# BLE_Bee_v1_0_sch.net
KiCad netlist of a schematic drawn in EAGLE
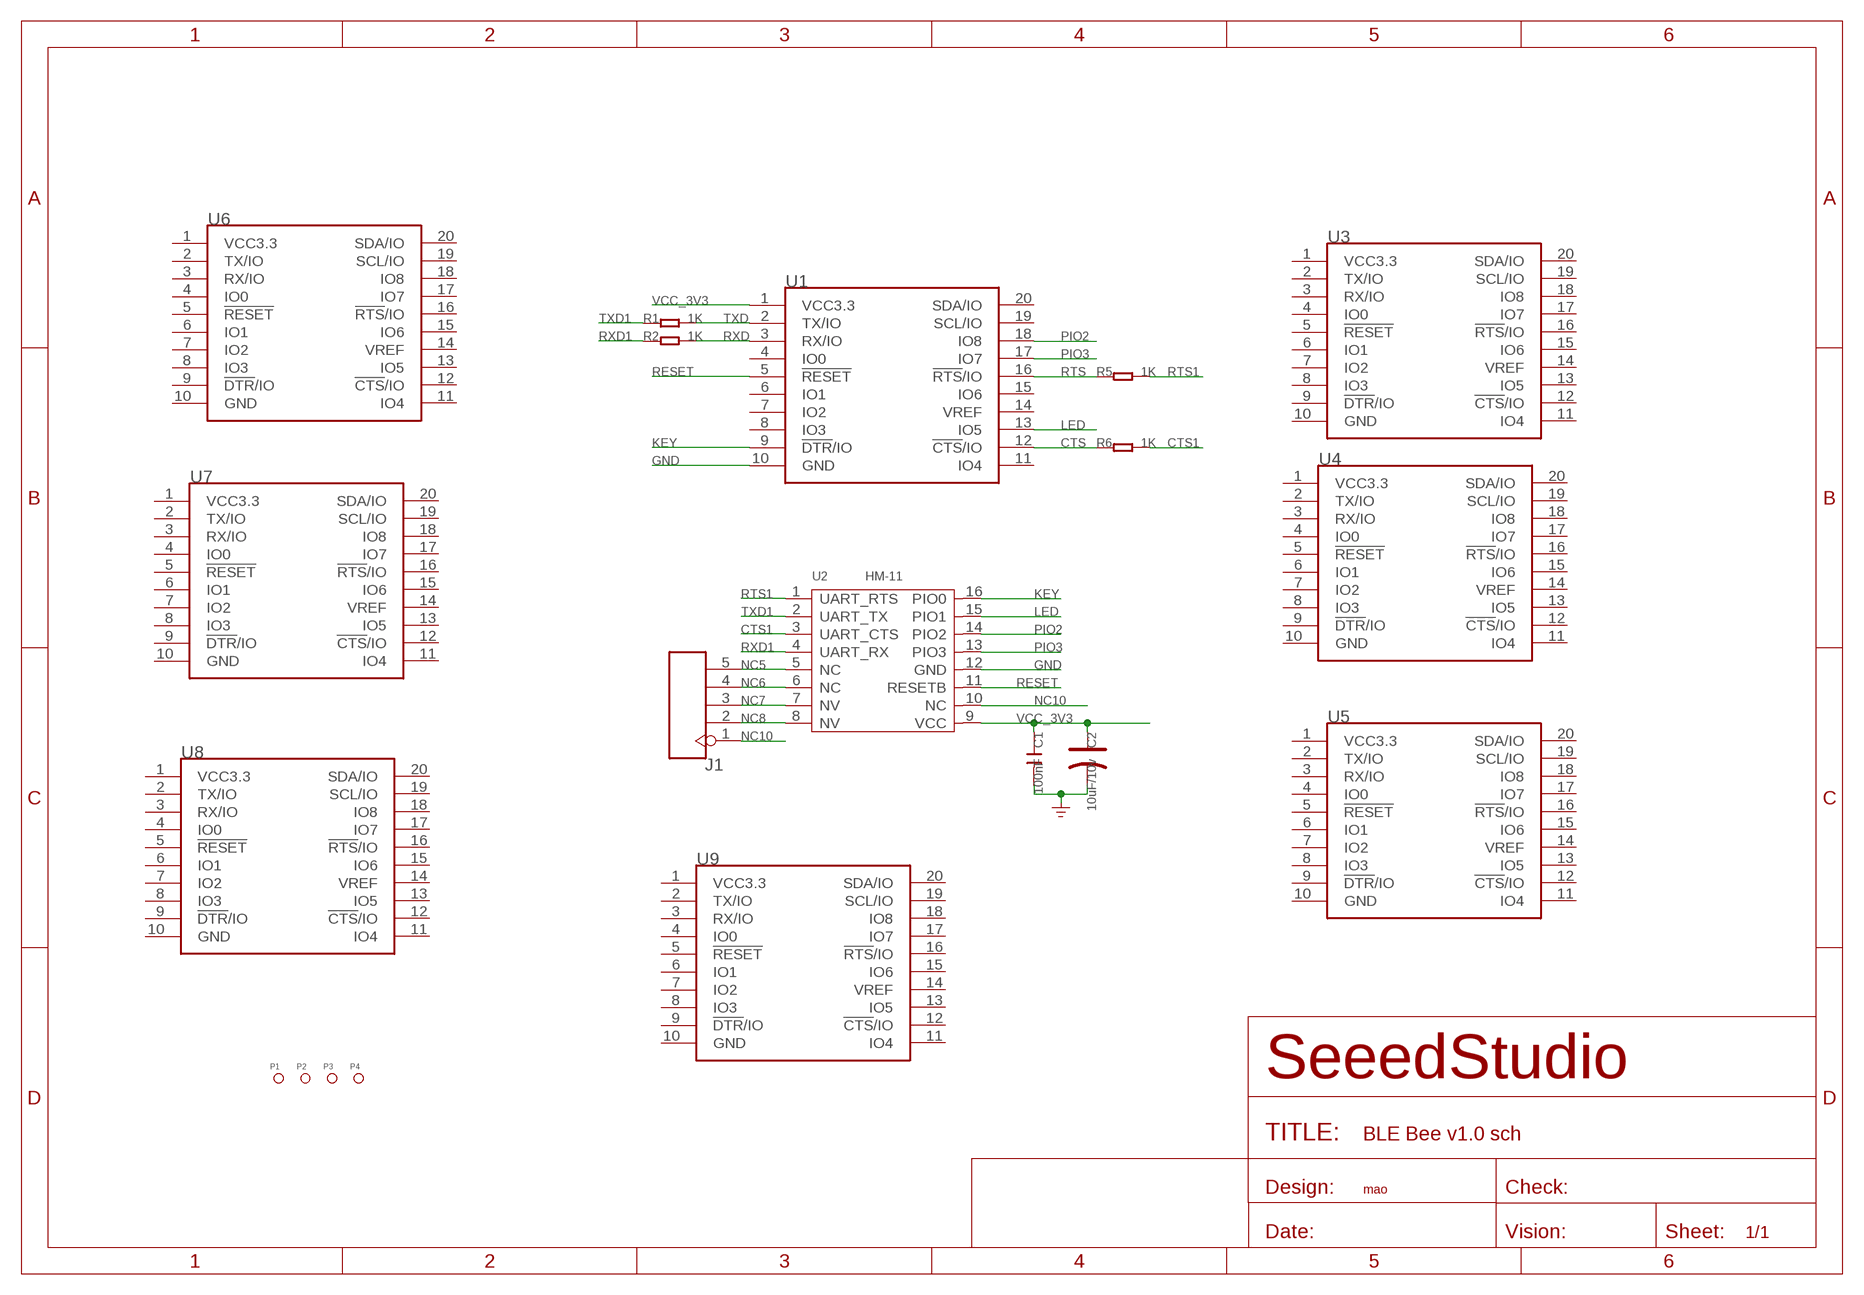
[diagram p0: schematic, sheet 1]

(export (version "E")
  (design (tool "Eeschema 10.0.6"))
  (components
    (comp (ref "C1")
      (value "100nF")
      (footprint "eagle-import:C0603")
      (libsource (lib "eagle-import") (part "C-0603"))
    )
    (comp (ref "C2")
      (value "10uF/10v")
      (footprint "eagle-import:AVX-A")
      (libsource (lib "eagle-import") (part "CAP-AVX-A"))
    )
    (comp (ref "J1")
      (value "HEADER-5P-2.0")
      (footprint "eagle-import:5P-2.0")
      (libsource (lib "eagle-import") (part "HEADER-5P-2.0"))
    )
    (comp (ref "P1")
      (value "PAD-MARK")
      (footprint "eagle-import:ROUND-MARK-1.0")
      (fields (field (name "PARTNO") "DNP"))
      (libsource (lib "eagle-import") (part "PAD-MARK"))
    )
    (comp (ref "P2")
      (value "PAD-MARK")
      (footprint "eagle-import:ROUND-MARK-1.0")
      (fields (field (name "PARTNO") "DNP"))
      (libsource (lib "eagle-import") (part "PAD-MARK"))
    )
    (comp (ref "P3")
      (value "PAD-MARK")
      (footprint "eagle-import:ROUND-MARK-1.0")
      (fields (field (name "PARTNO") "DNP"))
      (libsource (lib "eagle-import") (part "PAD-MARK"))
    )
    (comp (ref "P4")
      (value "PAD-MARK")
      (footprint "eagle-import:ROUND-MARK-1.0")
      (fields (field (name "PARTNO") "DNP"))
      (libsource (lib "eagle-import") (part "PAD-MARK"))
    )
    (comp (ref "R1")
      (value "1K")
      (footprint "eagle-import:R0603")
      (libsource (lib "eagle-import") (part "R-0603"))
    )
    (comp (ref "R2")
      (value "1K")
      (footprint "eagle-import:R0603")
      (libsource (lib "eagle-import") (part "R-0603"))
    )
    (comp (ref "R5")
      (value "1K")
      (footprint "eagle-import:R0603")
      (libsource (lib "eagle-import") (part "R-0603"))
    )
    (comp (ref "R6")
      (value "1K")
      (footprint "eagle-import:R0603")
      (libsource (lib "eagle-import") (part "R-0603"))
    )
    (comp (ref "U1")
      (value "BEE-OPENBEE-DIP")
      (footprint "eagle-import:20P-DIP-2.0")
      (libsource (lib "eagle-import") (part "BEE-OPENBEE-DIP"))
    )
    (comp (ref "U2")
      (value "HM-11")
      (footprint "eagle-import:16P-18.5X13.5X0.8")
      (libsource (lib "eagle-import") (part "HM-11"))
    )
    (comp (ref "U3")
      (value "BEE-OPENBEE-DIP")
      (footprint "eagle-import:20P-DIP-2.0")
      (libsource (lib "eagle-import") (part "BEE-OPENBEE-DIP"))
    )
    (comp (ref "U4")
      (value "BEE-OPENBEE-DIP")
      (footprint "eagle-import:20P-DIP-2.0")
      (libsource (lib "eagle-import") (part "BEE-OPENBEE-DIP"))
    )
    (comp (ref "U5")
      (value "BEE-OPENBEE-DIP")
      (footprint "eagle-import:20P-DIP-2.0")
      (libsource (lib "eagle-import") (part "BEE-OPENBEE-DIP"))
    )
    (comp (ref "U6")
      (value "BEE-OPENBEE-DIP")
      (footprint "eagle-import:20P-DIP-2.0")
      (libsource (lib "eagle-import") (part "BEE-OPENBEE-DIP"))
    )
    (comp (ref "U7")
      (value "BEE-OPENBEE-DIP")
      (footprint "eagle-import:20P-DIP-2.0")
      (libsource (lib "eagle-import") (part "BEE-OPENBEE-DIP"))
    )
    (comp (ref "U8")
      (value "BEE-OPENBEE-DIP")
      (footprint "eagle-import:20P-DIP-2.0")
      (libsource (lib "eagle-import") (part "BEE-OPENBEE-DIP"))
    )
    (comp (ref "U9")
      (value "BEE-OPENBEE-DIP")
      (footprint "eagle-import:20P-DIP-2.0")
      (libsource (lib "eagle-import") (part "BEE-OPENBEE-DIP"))
    )
  )
  (nets
    (net (code "1") (name "/CTS") (class "Default")
      (node (ref "R6") (pin "1") (pinfunction "1_1") (pintype "passive"))
      (node (ref "U1") (pin "12") (pinfunction "~{CTS}/IO_12") (pintype "bidirectional"))
    )
    (net (code "2") (name "/CTS1") (class "Default")
      (node (ref "R6") (pin "2") (pinfunction "2_2") (pintype "passive"))
      (node (ref "U2") (pin "3") (pinfunction "UART_CTS_3") (pintype "bidirectional"))
    )
    (net (code "3") (name "/KEY") (class "Default")
      (node (ref "U1") (pin "9") (pinfunction "~{DTR}/IO_9") (pintype "bidirectional"))
      (node (ref "U2") (pin "16") (pinfunction "PIO0_16") (pintype "bidirectional"))
    )
    (net (code "4") (name "/LED") (class "Default")
      (node (ref "U1") (pin "13") (pinfunction "IO5_13") (pintype "bidirectional"))
      (node (ref "U2") (pin "15") (pinfunction "PIO1_15") (pintype "bidirectional"))
    )
    (net (code "5") (name "/NC5") (class "Default")
      (node (ref "J1") (pin "5") (pinfunction "5_5") (pintype "bidirectional"))
      (node (ref "U2") (pin "5") (pinfunction "NC_5") (pintype "bidirectional"))
    )
    (net (code "6") (name "/NC6") (class "Default")
      (node (ref "J1") (pin "4") (pinfunction "4_4") (pintype "bidirectional"))
      (node (ref "U2") (pin "6") (pinfunction "NC_6") (pintype "bidirectional"))
    )
    (net (code "7") (name "/NC7") (class "Default")
      (node (ref "J1") (pin "3") (pinfunction "3_3") (pintype "bidirectional"))
      (node (ref "U2") (pin "7") (pinfunction "NV_7") (pintype "bidirectional"))
    )
    (net (code "8") (name "/NC8") (class "Default")
      (node (ref "J1") (pin "2") (pinfunction "2_2") (pintype "bidirectional"))
      (node (ref "U2") (pin "8") (pinfunction "NV_8") (pintype "bidirectional"))
    )
    (net (code "9") (name "/NC10") (class "Default")
      (node (ref "J1") (pin "1") (pinfunction "1_1") (pintype "bidirectional"))
      (node (ref "U2") (pin "10") (pinfunction "NC_10") (pintype "bidirectional"))
    )
    (net (code "10") (name "/PIO2") (class "Default")
      (node (ref "U1") (pin "18") (pinfunction "IO8_18") (pintype "bidirectional"))
      (node (ref "U2") (pin "14") (pinfunction "PIO2_14") (pintype "bidirectional"))
    )
    (net (code "11") (name "/PIO3") (class "Default")
      (node (ref "U1") (pin "17") (pinfunction "IO7_17") (pintype "bidirectional"))
      (node (ref "U2") (pin "13") (pinfunction "PIO3_13") (pintype "bidirectional"))
    )
    (net (code "12") (name "/RESET") (class "Default")
      (node (ref "U1") (pin "5") (pinfunction "~{RESET}_5") (pintype "bidirectional"))
      (node (ref "U2") (pin "11") (pinfunction "RESETB_11") (pintype "bidirectional"))
    )
    (net (code "13") (name "/RTS") (class "Default")
      (node (ref "R5") (pin "1") (pinfunction "1_1") (pintype "passive"))
      (node (ref "U1") (pin "16") (pinfunction "~{RTS}/IO_16") (pintype "bidirectional"))
    )
    (net (code "14") (name "/RTS1") (class "Default")
      (node (ref "R5") (pin "2") (pinfunction "2_2") (pintype "passive"))
      (node (ref "U2") (pin "1") (pinfunction "UART_RTS_1") (pintype "bidirectional"))
    )
    (net (code "15") (name "/RXD") (class "Default")
      (node (ref "R2") (pin "2") (pinfunction "2_2") (pintype "passive"))
      (node (ref "U1") (pin "3") (pinfunction "RX/IO_3") (pintype "bidirectional"))
    )
    (net (code "16") (name "/RXD1") (class "Default")
      (node (ref "R2") (pin "1") (pinfunction "1_1") (pintype "passive"))
      (node (ref "U2") (pin "4") (pinfunction "UART_RX_4") (pintype "bidirectional"))
    )
    (net (code "17") (name "/TXD") (class "Default")
      (node (ref "R1") (pin "2") (pinfunction "2_2") (pintype "passive"))
      (node (ref "U1") (pin "2") (pinfunction "TX/IO_2") (pintype "bidirectional"))
    )
    (net (code "18") (name "/TXD1") (class "Default")
      (node (ref "R1") (pin "1") (pinfunction "1_1") (pintype "passive"))
      (node (ref "U2") (pin "2") (pinfunction "UART_TX_2") (pintype "bidirectional"))
    )
    (net (code "19") (name "/VCC_3V3") (class "Default")
      (node (ref "C1") (pin "1") (pinfunction "1_1") (pintype "passive"))
      (node (ref "C2") (pin "+") (pinfunction "+_+") (pintype "passive"))
      (node (ref "U1") (pin "1") (pinfunction "VCC3.3_1") (pintype "bidirectional"))
      (node (ref "U2") (pin "9") (pinfunction "VCC_9") (pintype "bidirectional"))
    )
    (net (code "20") (name "GND_POWER") (class "Default")
      (node (ref "C1") (pin "2") (pinfunction "2_2") (pintype "passive"))
      (node (ref "C2") (pin "-") (pinfunction "-_-") (pintype "passive"))
      (node (ref "U1") (pin "10") (pinfunction "GND_10") (pintype "bidirectional"))
      (node (ref "U2") (pin "12") (pinfunction "GND_12") (pintype "bidirectional"))
    )
    (net (code "21") (name "unconnected-(U1-IO0-Pad4)") (class "Default")
      (node (ref "U1") (pin "4") (pinfunction "IO0_4") (pintype "bidirectional"))
    )
    (net (code "22") (name "unconnected-(U1-IO1-Pad6)") (class "Default")
      (node (ref "U1") (pin "6") (pinfunction "IO1_6") (pintype "bidirectional"))
    )
    (net (code "23") (name "unconnected-(U1-IO2-Pad7)") (class "Default")
      (node (ref "U1") (pin "7") (pinfunction "IO2_7") (pintype "bidirectional"))
    )
    (net (code "24") (name "unconnected-(U1-IO3-Pad8)") (class "Default")
      (node (ref "U1") (pin "8") (pinfunction "IO3_8") (pintype "bidirectional"))
    )
    (net (code "25") (name "unconnected-(U1-IO4-Pad11)") (class "Default")
      (node (ref "U1") (pin "11") (pinfunction "IO4_11") (pintype "bidirectional"))
    )
    (net (code "26") (name "unconnected-(U1-IO6-Pad15)") (class "Default")
      (node (ref "U1") (pin "15") (pinfunction "IO6_15") (pintype "bidirectional"))
    )
    (net (code "27") (name "unconnected-(U1-SCL{slash}IO-Pad19)") (class "Default")
      (node (ref "U1") (pin "19") (pinfunction "SCL/IO_19") (pintype "bidirectional"))
    )
    (net (code "28") (name "unconnected-(U1-SDA{slash}IO-Pad20)") (class "Default")
      (node (ref "U1") (pin "20") (pinfunction "SDA/IO_20") (pintype "bidirectional"))
    )
    (net (code "29") (name "unconnected-(U1-VREF-Pad14)") (class "Default")
      (node (ref "U1") (pin "14") (pinfunction "VREF_14") (pintype "bidirectional"))
    )
    (net (code "30") (name "unconnected-(U3-GND-Pad10)") (class "Default")
      (node (ref "U3") (pin "10") (pinfunction "GND_10") (pintype "bidirectional"))
    )
    (net (code "31") (name "unconnected-(U3-IO0-Pad4)") (class "Default")
      (node (ref "U3") (pin "4") (pinfunction "IO0_4") (pintype "bidirectional"))
    )
    (net (code "32") (name "unconnected-(U3-IO1-Pad6)") (class "Default")
      (node (ref "U3") (pin "6") (pinfunction "IO1_6") (pintype "bidirectional"))
    )
    (net (code "33") (name "unconnected-(U3-IO2-Pad7)") (class "Default")
      (node (ref "U3") (pin "7") (pinfunction "IO2_7") (pintype "bidirectional"))
    )
    (net (code "34") (name "unconnected-(U3-IO3-Pad8)") (class "Default")
      (node (ref "U3") (pin "8") (pinfunction "IO3_8") (pintype "bidirectional"))
    )
    (net (code "35") (name "unconnected-(U3-IO4-Pad11)") (class "Default")
      (node (ref "U3") (pin "11") (pinfunction "IO4_11") (pintype "bidirectional"))
    )
    (net (code "36") (name "unconnected-(U3-IO5-Pad13)") (class "Default")
      (node (ref "U3") (pin "13") (pinfunction "IO5_13") (pintype "bidirectional"))
    )
    (net (code "37") (name "unconnected-(U3-IO6-Pad15)") (class "Default")
      (node (ref "U3") (pin "15") (pinfunction "IO6_15") (pintype "bidirectional"))
    )
    (net (code "38") (name "unconnected-(U3-IO7-Pad17)") (class "Default")
      (node (ref "U3") (pin "17") (pinfunction "IO7_17") (pintype "bidirectional"))
    )
    (net (code "39") (name "unconnected-(U3-IO8-Pad18)") (class "Default")
      (node (ref "U3") (pin "18") (pinfunction "IO8_18") (pintype "bidirectional"))
    )
    (net (code "40") (name "unconnected-(U3-RX{slash}IO-Pad3)") (class "Default")
      (node (ref "U3") (pin "3") (pinfunction "RX/IO_3") (pintype "bidirectional"))
    )
    (net (code "41") (name "unconnected-(U3-SCL{slash}IO-Pad19)") (class "Default")
      (node (ref "U3") (pin "19") (pinfunction "SCL/IO_19") (pintype "bidirectional"))
    )
    (net (code "42") (name "unconnected-(U3-SDA{slash}IO-Pad20)") (class "Default")
      (node (ref "U3") (pin "20") (pinfunction "SDA/IO_20") (pintype "bidirectional"))
    )
    (net (code "43") (name "unconnected-(U3-TX{slash}IO-Pad2)") (class "Default")
      (node (ref "U3") (pin "2") (pinfunction "TX/IO_2") (pintype "bidirectional"))
    )
    (net (code "44") (name "unconnected-(U3-VCC3.3-Pad1)") (class "Default")
      (node (ref "U3") (pin "1") (pinfunction "VCC3.3_1") (pintype "bidirectional"))
    )
    (net (code "45") (name "unconnected-(U3-VREF-Pad14)") (class "Default")
      (node (ref "U3") (pin "14") (pinfunction "VREF_14") (pintype "bidirectional"))
    )
    (net (code "46") (name "unconnected-(U3-~{CTS}{slash}IO-Pad12)") (class "Default")
      (node (ref "U3") (pin "12") (pinfunction "~{CTS}/IO_12") (pintype "bidirectional"))
    )
    (net (code "47") (name "unconnected-(U3-~{DTR}{slash}IO-Pad9)") (class "Default")
      (node (ref "U3") (pin "9") (pinfunction "~{DTR}/IO_9") (pintype "bidirectional"))
    )
    (net (code "48") (name "unconnected-(U3-~{RESET}-Pad5)") (class "Default")
      (node (ref "U3") (pin "5") (pinfunction "~{RESET}_5") (pintype "bidirectional"))
    )
    (net (code "49") (name "unconnected-(U3-~{RTS}{slash}IO-Pad16)") (class "Default")
      (node (ref "U3") (pin "16") (pinfunction "~{RTS}/IO_16") (pintype "bidirectional"))
    )
    (net (code "50") (name "unconnected-(U4-GND-Pad10)") (class "Default")
      (node (ref "U4") (pin "10") (pinfunction "GND_10") (pintype "bidirectional"))
    )
    (net (code "51") (name "unconnected-(U4-IO0-Pad4)") (class "Default")
      (node (ref "U4") (pin "4") (pinfunction "IO0_4") (pintype "bidirectional"))
    )
    (net (code "52") (name "unconnected-(U4-IO1-Pad6)") (class "Default")
      (node (ref "U4") (pin "6") (pinfunction "IO1_6") (pintype "bidirectional"))
    )
    (net (code "53") (name "unconnected-(U4-IO2-Pad7)") (class "Default")
      (node (ref "U4") (pin "7") (pinfunction "IO2_7") (pintype "bidirectional"))
    )
    (net (code "54") (name "unconnected-(U4-IO3-Pad8)") (class "Default")
      (node (ref "U4") (pin "8") (pinfunction "IO3_8") (pintype "bidirectional"))
    )
    (net (code "55") (name "unconnected-(U4-IO4-Pad11)") (class "Default")
      (node (ref "U4") (pin "11") (pinfunction "IO4_11") (pintype "bidirectional"))
    )
    (net (code "56") (name "unconnected-(U4-IO5-Pad13)") (class "Default")
      (node (ref "U4") (pin "13") (pinfunction "IO5_13") (pintype "bidirectional"))
    )
    (net (code "57") (name "unconnected-(U4-IO6-Pad15)") (class "Default")
      (node (ref "U4") (pin "15") (pinfunction "IO6_15") (pintype "bidirectional"))
    )
    (net (code "58") (name "unconnected-(U4-IO7-Pad17)") (class "Default")
      (node (ref "U4") (pin "17") (pinfunction "IO7_17") (pintype "bidirectional"))
    )
    (net (code "59") (name "unconnected-(U4-IO8-Pad18)") (class "Default")
      (node (ref "U4") (pin "18") (pinfunction "IO8_18") (pintype "bidirectional"))
    )
    (net (code "60") (name "unconnected-(U4-RX{slash}IO-Pad3)") (class "Default")
      (node (ref "U4") (pin "3") (pinfunction "RX/IO_3") (pintype "bidirectional"))
    )
    (net (code "61") (name "unconnected-(U4-SCL{slash}IO-Pad19)") (class "Default")
      (node (ref "U4") (pin "19") (pinfunction "SCL/IO_19") (pintype "bidirectional"))
    )
    (net (code "62") (name "unconnected-(U4-SDA{slash}IO-Pad20)") (class "Default")
      (node (ref "U4") (pin "20") (pinfunction "SDA/IO_20") (pintype "bidirectional"))
    )
    (net (code "63") (name "unconnected-(U4-TX{slash}IO-Pad2)") (class "Default")
      (node (ref "U4") (pin "2") (pinfunction "TX/IO_2") (pintype "bidirectional"))
    )
    (net (code "64") (name "unconnected-(U4-VCC3.3-Pad1)") (class "Default")
      (node (ref "U4") (pin "1") (pinfunction "VCC3.3_1") (pintype "bidirectional"))
    )
    (net (code "65") (name "unconnected-(U4-VREF-Pad14)") (class "Default")
      (node (ref "U4") (pin "14") (pinfunction "VREF_14") (pintype "bidirectional"))
    )
    (net (code "66") (name "unconnected-(U4-~{CTS}{slash}IO-Pad12)") (class "Default")
      (node (ref "U4") (pin "12") (pinfunction "~{CTS}/IO_12") (pintype "bidirectional"))
    )
    (net (code "67") (name "unconnected-(U4-~{DTR}{slash}IO-Pad9)") (class "Default")
      (node (ref "U4") (pin "9") (pinfunction "~{DTR}/IO_9") (pintype "bidirectional"))
    )
    (net (code "68") (name "unconnected-(U4-~{RESET}-Pad5)") (class "Default")
      (node (ref "U4") (pin "5") (pinfunction "~{RESET}_5") (pintype "bidirectional"))
    )
    (net (code "69") (name "unconnected-(U4-~{RTS}{slash}IO-Pad16)") (class "Default")
      (node (ref "U4") (pin "16") (pinfunction "~{RTS}/IO_16") (pintype "bidirectional"))
    )
    (net (code "70") (name "unconnected-(U5-GND-Pad10)") (class "Default")
      (node (ref "U5") (pin "10") (pinfunction "GND_10") (pintype "bidirectional"))
    )
    (net (code "71") (name "unconnected-(U5-IO0-Pad4)") (class "Default")
      (node (ref "U5") (pin "4") (pinfunction "IO0_4") (pintype "bidirectional"))
    )
    (net (code "72") (name "unconnected-(U5-IO1-Pad6)") (class "Default")
      (node (ref "U5") (pin "6") (pinfunction "IO1_6") (pintype "bidirectional"))
    )
    (net (code "73") (name "unconnected-(U5-IO2-Pad7)") (class "Default")
      (node (ref "U5") (pin "7") (pinfunction "IO2_7") (pintype "bidirectional"))
    )
    (net (code "74") (name "unconnected-(U5-IO3-Pad8)") (class "Default")
      (node (ref "U5") (pin "8") (pinfunction "IO3_8") (pintype "bidirectional"))
    )
    (net (code "75") (name "unconnected-(U5-IO4-Pad11)") (class "Default")
      (node (ref "U5") (pin "11") (pinfunction "IO4_11") (pintype "bidirectional"))
    )
    (net (code "76") (name "unconnected-(U5-IO5-Pad13)") (class "Default")
      (node (ref "U5") (pin "13") (pinfunction "IO5_13") (pintype "bidirectional"))
    )
    (net (code "77") (name "unconnected-(U5-IO6-Pad15)") (class "Default")
      (node (ref "U5") (pin "15") (pinfunction "IO6_15") (pintype "bidirectional"))
    )
    (net (code "78") (name "unconnected-(U5-IO7-Pad17)") (class "Default")
      (node (ref "U5") (pin "17") (pinfunction "IO7_17") (pintype "bidirectional"))
    )
    (net (code "79") (name "unconnected-(U5-IO8-Pad18)") (class "Default")
      (node (ref "U5") (pin "18") (pinfunction "IO8_18") (pintype "bidirectional"))
    )
    (net (code "80") (name "unconnected-(U5-RX{slash}IO-Pad3)") (class "Default")
      (node (ref "U5") (pin "3") (pinfunction "RX/IO_3") (pintype "bidirectional"))
    )
    (net (code "81") (name "unconnected-(U5-SCL{slash}IO-Pad19)") (class "Default")
      (node (ref "U5") (pin "19") (pinfunction "SCL/IO_19") (pintype "bidirectional"))
    )
    (net (code "82") (name "unconnected-(U5-SDA{slash}IO-Pad20)") (class "Default")
      (node (ref "U5") (pin "20") (pinfunction "SDA/IO_20") (pintype "bidirectional"))
    )
    (net (code "83") (name "unconnected-(U5-TX{slash}IO-Pad2)") (class "Default")
      (node (ref "U5") (pin "2") (pinfunction "TX/IO_2") (pintype "bidirectional"))
    )
    (net (code "84") (name "unconnected-(U5-VCC3.3-Pad1)") (class "Default")
      (node (ref "U5") (pin "1") (pinfunction "VCC3.3_1") (pintype "bidirectional"))
    )
    (net (code "85") (name "unconnected-(U5-VREF-Pad14)") (class "Default")
      (node (ref "U5") (pin "14") (pinfunction "VREF_14") (pintype "bidirectional"))
    )
    (net (code "86") (name "unconnected-(U5-~{CTS}{slash}IO-Pad12)") (class "Default")
      (node (ref "U5") (pin "12") (pinfunction "~{CTS}/IO_12") (pintype "bidirectional"))
    )
    (net (code "87") (name "unconnected-(U5-~{DTR}{slash}IO-Pad9)") (class "Default")
      (node (ref "U5") (pin "9") (pinfunction "~{DTR}/IO_9") (pintype "bidirectional"))
    )
    (net (code "88") (name "unconnected-(U5-~{RESET}-Pad5)") (class "Default")
      (node (ref "U5") (pin "5") (pinfunction "~{RESET}_5") (pintype "bidirectional"))
    )
    (net (code "89") (name "unconnected-(U5-~{RTS}{slash}IO-Pad16)") (class "Default")
      (node (ref "U5") (pin "16") (pinfunction "~{RTS}/IO_16") (pintype "bidirectional"))
    )
    (net (code "90") (name "unconnected-(U6-GND-Pad10)") (class "Default")
      (node (ref "U6") (pin "10") (pinfunction "GND_10") (pintype "bidirectional"))
    )
    (net (code "91") (name "unconnected-(U6-IO0-Pad4)") (class "Default")
      (node (ref "U6") (pin "4") (pinfunction "IO0_4") (pintype "bidirectional"))
    )
    (net (code "92") (name "unconnected-(U6-IO1-Pad6)") (class "Default")
      (node (ref "U6") (pin "6") (pinfunction "IO1_6") (pintype "bidirectional"))
    )
    (net (code "93") (name "unconnected-(U6-IO2-Pad7)") (class "Default")
      (node (ref "U6") (pin "7") (pinfunction "IO2_7") (pintype "bidirectional"))
    )
    (net (code "94") (name "unconnected-(U6-IO3-Pad8)") (class "Default")
      (node (ref "U6") (pin "8") (pinfunction "IO3_8") (pintype "bidirectional"))
    )
    (net (code "95") (name "unconnected-(U6-IO4-Pad11)") (class "Default")
      (node (ref "U6") (pin "11") (pinfunction "IO4_11") (pintype "bidirectional"))
    )
    (net (code "96") (name "unconnected-(U6-IO5-Pad13)") (class "Default")
      (node (ref "U6") (pin "13") (pinfunction "IO5_13") (pintype "bidirectional"))
    )
    (net (code "97") (name "unconnected-(U6-IO6-Pad15)") (class "Default")
      (node (ref "U6") (pin "15") (pinfunction "IO6_15") (pintype "bidirectional"))
    )
    (net (code "98") (name "unconnected-(U6-IO7-Pad17)") (class "Default")
      (node (ref "U6") (pin "17") (pinfunction "IO7_17") (pintype "bidirectional"))
    )
    (net (code "99") (name "unconnected-(U6-IO8-Pad18)") (class "Default")
      (node (ref "U6") (pin "18") (pinfunction "IO8_18") (pintype "bidirectional"))
    )
    (net (code "100") (name "unconnected-(U6-RX{slash}IO-Pad3)") (class "Default")
      (node (ref "U6") (pin "3") (pinfunction "RX/IO_3") (pintype "bidirectional"))
    )
    (net (code "101") (name "unconnected-(U6-SCL{slash}IO-Pad19)") (class "Default")
      (node (ref "U6") (pin "19") (pinfunction "SCL/IO_19") (pintype "bidirectional"))
    )
    (net (code "102") (name "unconnected-(U6-SDA{slash}IO-Pad20)") (class "Default")
      (node (ref "U6") (pin "20") (pinfunction "SDA/IO_20") (pintype "bidirectional"))
    )
    (net (code "103") (name "unconnected-(U6-TX{slash}IO-Pad2)") (class "Default")
      (node (ref "U6") (pin "2") (pinfunction "TX/IO_2") (pintype "bidirectional"))
    )
    (net (code "104") (name "unconnected-(U6-VCC3.3-Pad1)") (class "Default")
      (node (ref "U6") (pin "1") (pinfunction "VCC3.3_1") (pintype "bidirectional"))
    )
    (net (code "105") (name "unconnected-(U6-VREF-Pad14)") (class "Default")
      (node (ref "U6") (pin "14") (pinfunction "VREF_14") (pintype "bidirectional"))
    )
    (net (code "106") (name "unconnected-(U6-~{CTS}{slash}IO-Pad12)") (class "Default")
      (node (ref "U6") (pin "12") (pinfunction "~{CTS}/IO_12") (pintype "bidirectional"))
    )
    (net (code "107") (name "unconnected-(U6-~{DTR}{slash}IO-Pad9)") (class "Default")
      (node (ref "U6") (pin "9") (pinfunction "~{DTR}/IO_9") (pintype "bidirectional"))
    )
    (net (code "108") (name "unconnected-(U6-~{RESET}-Pad5)") (class "Default")
      (node (ref "U6") (pin "5") (pinfunction "~{RESET}_5") (pintype "bidirectional"))
    )
    (net (code "109") (name "unconnected-(U6-~{RTS}{slash}IO-Pad16)") (class "Default")
      (node (ref "U6") (pin "16") (pinfunction "~{RTS}/IO_16") (pintype "bidirectional"))
    )
    (net (code "110") (name "unconnected-(U7-GND-Pad10)") (class "Default")
      (node (ref "U7") (pin "10") (pinfunction "GND_10") (pintype "bidirectional"))
    )
    (net (code "111") (name "unconnected-(U7-IO0-Pad4)") (class "Default")
      (node (ref "U7") (pin "4") (pinfunction "IO0_4") (pintype "bidirectional"))
    )
    (net (code "112") (name "unconnected-(U7-IO1-Pad6)") (class "Default")
      (node (ref "U7") (pin "6") (pinfunction "IO1_6") (pintype "bidirectional"))
    )
    (net (code "113") (name "unconnected-(U7-IO2-Pad7)") (class "Default")
      (node (ref "U7") (pin "7") (pinfunction "IO2_7") (pintype "bidirectional"))
    )
    (net (code "114") (name "unconnected-(U7-IO3-Pad8)") (class "Default")
      (node (ref "U7") (pin "8") (pinfunction "IO3_8") (pintype "bidirectional"))
    )
    (net (code "115") (name "unconnected-(U7-IO4-Pad11)") (class "Default")
      (node (ref "U7") (pin "11") (pinfunction "IO4_11") (pintype "bidirectional"))
    )
    (net (code "116") (name "unconnected-(U7-IO5-Pad13)") (class "Default")
      (node (ref "U7") (pin "13") (pinfunction "IO5_13") (pintype "bidirectional"))
    )
    (net (code "117") (name "unconnected-(U7-IO6-Pad15)") (class "Default")
      (node (ref "U7") (pin "15") (pinfunction "IO6_15") (pintype "bidirectional"))
    )
    (net (code "118") (name "unconnected-(U7-IO7-Pad17)") (class "Default")
      (node (ref "U7") (pin "17") (pinfunction "IO7_17") (pintype "bidirectional"))
    )
    (net (code "119") (name "unconnected-(U7-IO8-Pad18)") (class "Default")
      (node (ref "U7") (pin "18") (pinfunction "IO8_18") (pintype "bidirectional"))
    )
    (net (code "120") (name "unconnected-(U7-RX{slash}IO-Pad3)") (class "Default")
      (node (ref "U7") (pin "3") (pinfunction "RX/IO_3") (pintype "bidirectional"))
    )
    (net (code "121") (name "unconnected-(U7-SCL{slash}IO-Pad19)") (class "Default")
      (node (ref "U7") (pin "19") (pinfunction "SCL/IO_19") (pintype "bidirectional"))
    )
    (net (code "122") (name "unconnected-(U7-SDA{slash}IO-Pad20)") (class "Default")
      (node (ref "U7") (pin "20") (pinfunction "SDA/IO_20") (pintype "bidirectional"))
    )
    (net (code "123") (name "unconnected-(U7-TX{slash}IO-Pad2)") (class "Default")
      (node (ref "U7") (pin "2") (pinfunction "TX/IO_2") (pintype "bidirectional"))
    )
    (net (code "124") (name "unconnected-(U7-VCC3.3-Pad1)") (class "Default")
      (node (ref "U7") (pin "1") (pinfunction "VCC3.3_1") (pintype "bidirectional"))
    )
    (net (code "125") (name "unconnected-(U7-VREF-Pad14)") (class "Default")
      (node (ref "U7") (pin "14") (pinfunction "VREF_14") (pintype "bidirectional"))
    )
    (net (code "126") (name "unconnected-(U7-~{CTS}{slash}IO-Pad12)") (class "Default")
      (node (ref "U7") (pin "12") (pinfunction "~{CTS}/IO_12") (pintype "bidirectional"))
    )
    (net (code "127") (name "unconnected-(U7-~{DTR}{slash}IO-Pad9)") (class "Default")
      (node (ref "U7") (pin "9") (pinfunction "~{DTR}/IO_9") (pintype "bidirectional"))
    )
    (net (code "128") (name "unconnected-(U7-~{RESET}-Pad5)") (class "Default")
      (node (ref "U7") (pin "5") (pinfunction "~{RESET}_5") (pintype "bidirectional"))
    )
    (net (code "129") (name "unconnected-(U7-~{RTS}{slash}IO-Pad16)") (class "Default")
      (node (ref "U7") (pin "16") (pinfunction "~{RTS}/IO_16") (pintype "bidirectional"))
    )
    (net (code "130") (name "unconnected-(U8-GND-Pad10)") (class "Default")
      (node (ref "U8") (pin "10") (pinfunction "GND_10") (pintype "bidirectional"))
    )
    (net (code "131") (name "unconnected-(U8-IO0-Pad4)") (class "Default")
      (node (ref "U8") (pin "4") (pinfunction "IO0_4") (pintype "bidirectional"))
    )
    (net (code "132") (name "unconnected-(U8-IO1-Pad6)") (class "Default")
      (node (ref "U8") (pin "6") (pinfunction "IO1_6") (pintype "bidirectional"))
    )
    (net (code "133") (name "unconnected-(U8-IO2-Pad7)") (class "Default")
      (node (ref "U8") (pin "7") (pinfunction "IO2_7") (pintype "bidirectional"))
    )
    (net (code "134") (name "unconnected-(U8-IO3-Pad8)") (class "Default")
      (node (ref "U8") (pin "8") (pinfunction "IO3_8") (pintype "bidirectional"))
    )
    (net (code "135") (name "unconnected-(U8-IO4-Pad11)") (class "Default")
      (node (ref "U8") (pin "11") (pinfunction "IO4_11") (pintype "bidirectional"))
    )
    (net (code "136") (name "unconnected-(U8-IO5-Pad13)") (class "Default")
      (node (ref "U8") (pin "13") (pinfunction "IO5_13") (pintype "bidirectional"))
    )
    (net (code "137") (name "unconnected-(U8-IO6-Pad15)") (class "Default")
      (node (ref "U8") (pin "15") (pinfunction "IO6_15") (pintype "bidirectional"))
    )
    (net (code "138") (name "unconnected-(U8-IO7-Pad17)") (class "Default")
      (node (ref "U8") (pin "17") (pinfunction "IO7_17") (pintype "bidirectional"))
    )
    (net (code "139") (name "unconnected-(U8-IO8-Pad18)") (class "Default")
      (node (ref "U8") (pin "18") (pinfunction "IO8_18") (pintype "bidirectional"))
    )
    (net (code "140") (name "unconnected-(U8-RX{slash}IO-Pad3)") (class "Default")
      (node (ref "U8") (pin "3") (pinfunction "RX/IO_3") (pintype "bidirectional"))
    )
    (net (code "141") (name "unconnected-(U8-SCL{slash}IO-Pad19)") (class "Default")
      (node (ref "U8") (pin "19") (pinfunction "SCL/IO_19") (pintype "bidirectional"))
    )
    (net (code "142") (name "unconnected-(U8-SDA{slash}IO-Pad20)") (class "Default")
      (node (ref "U8") (pin "20") (pinfunction "SDA/IO_20") (pintype "bidirectional"))
    )
    (net (code "143") (name "unconnected-(U8-TX{slash}IO-Pad2)") (class "Default")
      (node (ref "U8") (pin "2") (pinfunction "TX/IO_2") (pintype "bidirectional"))
    )
    (net (code "144") (name "unconnected-(U8-VCC3.3-Pad1)") (class "Default")
      (node (ref "U8") (pin "1") (pinfunction "VCC3.3_1") (pintype "bidirectional"))
    )
    (net (code "145") (name "unconnected-(U8-VREF-Pad14)") (class "Default")
      (node (ref "U8") (pin "14") (pinfunction "VREF_14") (pintype "bidirectional"))
    )
    (net (code "146") (name "unconnected-(U8-~{CTS}{slash}IO-Pad12)") (class "Default")
      (node (ref "U8") (pin "12") (pinfunction "~{CTS}/IO_12") (pintype "bidirectional"))
    )
    (net (code "147") (name "unconnected-(U8-~{DTR}{slash}IO-Pad9)") (class "Default")
      (node (ref "U8") (pin "9") (pinfunction "~{DTR}/IO_9") (pintype "bidirectional"))
    )
    (net (code "148") (name "unconnected-(U8-~{RESET}-Pad5)") (class "Default")
      (node (ref "U8") (pin "5") (pinfunction "~{RESET}_5") (pintype "bidirectional"))
    )
    (net (code "149") (name "unconnected-(U8-~{RTS}{slash}IO-Pad16)") (class "Default")
      (node (ref "U8") (pin "16") (pinfunction "~{RTS}/IO_16") (pintype "bidirectional"))
    )
    (net (code "150") (name "unconnected-(U9-GND-Pad10)") (class "Default")
      (node (ref "U9") (pin "10") (pinfunction "GND_10") (pintype "bidirectional"))
    )
    (net (code "151") (name "unconnected-(U9-IO0-Pad4)") (class "Default")
      (node (ref "U9") (pin "4") (pinfunction "IO0_4") (pintype "bidirectional"))
    )
    (net (code "152") (name "unconnected-(U9-IO1-Pad6)") (class "Default")
      (node (ref "U9") (pin "6") (pinfunction "IO1_6") (pintype "bidirectional"))
    )
    (net (code "153") (name "unconnected-(U9-IO2-Pad7)") (class "Default")
      (node (ref "U9") (pin "7") (pinfunction "IO2_7") (pintype "bidirectional"))
    )
    (net (code "154") (name "unconnected-(U9-IO3-Pad8)") (class "Default")
      (node (ref "U9") (pin "8") (pinfunction "IO3_8") (pintype "bidirectional"))
    )
    (net (code "155") (name "unconnected-(U9-IO4-Pad11)") (class "Default")
      (node (ref "U9") (pin "11") (pinfunction "IO4_11") (pintype "bidirectional"))
    )
    (net (code "156") (name "unconnected-(U9-IO5-Pad13)") (class "Default")
      (node (ref "U9") (pin "13") (pinfunction "IO5_13") (pintype "bidirectional"))
    )
    (net (code "157") (name "unconnected-(U9-IO6-Pad15)") (class "Default")
      (node (ref "U9") (pin "15") (pinfunction "IO6_15") (pintype "bidirectional"))
    )
    (net (code "158") (name "unconnected-(U9-IO7-Pad17)") (class "Default")
      (node (ref "U9") (pin "17") (pinfunction "IO7_17") (pintype "bidirectional"))
    )
    (net (code "159") (name "unconnected-(U9-IO8-Pad18)") (class "Default")
      (node (ref "U9") (pin "18") (pinfunction "IO8_18") (pintype "bidirectional"))
    )
    (net (code "160") (name "unconnected-(U9-RX{slash}IO-Pad3)") (class "Default")
      (node (ref "U9") (pin "3") (pinfunction "RX/IO_3") (pintype "bidirectional"))
    )
    (net (code "161") (name "unconnected-(U9-SCL{slash}IO-Pad19)") (class "Default")
      (node (ref "U9") (pin "19") (pinfunction "SCL/IO_19") (pintype "bidirectional"))
    )
    (net (code "162") (name "unconnected-(U9-SDA{slash}IO-Pad20)") (class "Default")
      (node (ref "U9") (pin "20") (pinfunction "SDA/IO_20") (pintype "bidirectional"))
    )
    (net (code "163") (name "unconnected-(U9-TX{slash}IO-Pad2)") (class "Default")
      (node (ref "U9") (pin "2") (pinfunction "TX/IO_2") (pintype "bidirectional"))
    )
    (net (code "164") (name "unconnected-(U9-VCC3.3-Pad1)") (class "Default")
      (node (ref "U9") (pin "1") (pinfunction "VCC3.3_1") (pintype "bidirectional"))
    )
    (net (code "165") (name "unconnected-(U9-VREF-Pad14)") (class "Default")
      (node (ref "U9") (pin "14") (pinfunction "VREF_14") (pintype "bidirectional"))
    )
    (net (code "166") (name "unconnected-(U9-~{CTS}{slash}IO-Pad12)") (class "Default")
      (node (ref "U9") (pin "12") (pinfunction "~{CTS}/IO_12") (pintype "bidirectional"))
    )
    (net (code "167") (name "unconnected-(U9-~{DTR}{slash}IO-Pad9)") (class "Default")
      (node (ref "U9") (pin "9") (pinfunction "~{DTR}/IO_9") (pintype "bidirectional"))
    )
    (net (code "168") (name "unconnected-(U9-~{RESET}-Pad5)") (class "Default")
      (node (ref "U9") (pin "5") (pinfunction "~{RESET}_5") (pintype "bidirectional"))
    )
    (net (code "169") (name "unconnected-(U9-~{RTS}{slash}IO-Pad16)") (class "Default")
      (node (ref "U9") (pin "16") (pinfunction "~{RTS}/IO_16") (pintype "bidirectional"))
    )
  )
)
